# DriverOK-DemuxOK-VIA71.net
KiCad netlist of a schematic drawn in EAGLE
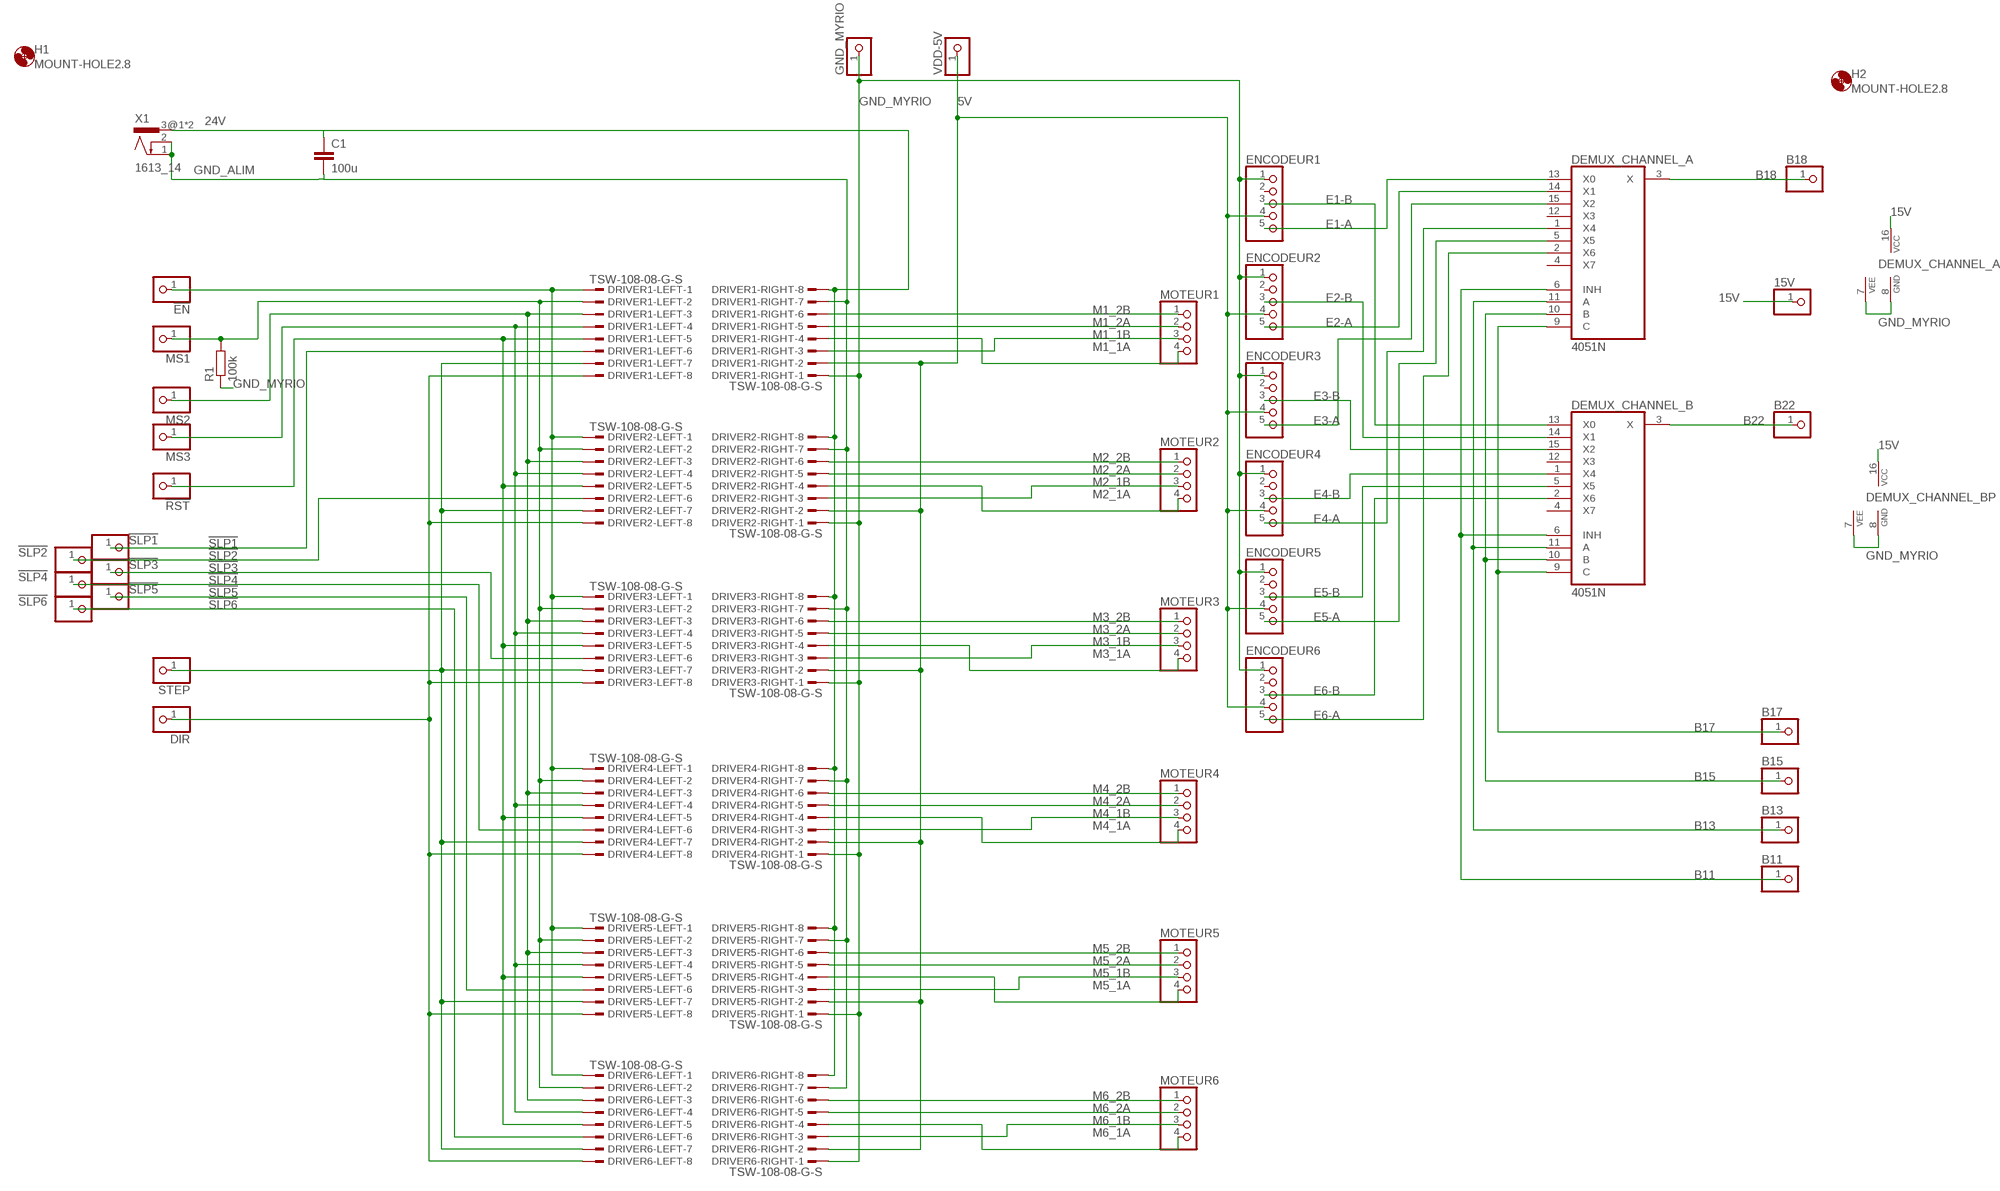
[diagram p0: schematic, sheet 1]

(export (version "E")
  (design (tool "Eeschema 10.0.6"))
  (components
    (comp (ref "!EN")
      (value "PINHD-1X1")
      (footprint "eagle-import:1X01")
      (libsource (lib "eagle-import") (part "PINHD-1X1"))
    )
    (comp (ref "!RST")
      (value "PINHD-1X1")
      (footprint "eagle-import:1X01")
      (libsource (lib "eagle-import") (part "PINHD-1X1"))
    )
    (comp (ref "!SLP1")
      (value "PINHD-1X1")
      (footprint "eagle-import:1X01")
      (libsource (lib "eagle-import") (part "PINHD-1X1"))
    )
    (comp (ref "!SLP2")
      (value "PINHD-1X1")
      (footprint "eagle-import:1X01")
      (libsource (lib "eagle-import") (part "PINHD-1X1"))
    )
    (comp (ref "!SLP3")
      (value "PINHD-1X1")
      (footprint "eagle-import:1X01")
      (libsource (lib "eagle-import") (part "PINHD-1X1"))
    )
    (comp (ref "!SLP4")
      (value "PINHD-1X1")
      (footprint "eagle-import:1X01")
      (libsource (lib "eagle-import") (part "PINHD-1X1"))
    )
    (comp (ref "!SLP5")
      (value "PINHD-1X1")
      (footprint "eagle-import:1X01")
      (libsource (lib "eagle-import") (part "PINHD-1X1"))
    )
    (comp (ref "!SLP6")
      (value "PINHD-1X1")
      (footprint "eagle-import:1X01")
      (libsource (lib "eagle-import") (part "PINHD-1X1"))
    )
    (comp (ref "15V")
      (value "PINHD-1X1")
      (footprint "eagle-import:1X01")
      (libsource (lib "eagle-import") (part "PINHD-1X1"))
    )
    (comp (ref "B11")
      (value "PINHD-1X1")
      (footprint "eagle-import:1X01")
      (libsource (lib "eagle-import") (part "PINHD-1X1"))
    )
    (comp (ref "B13")
      (value "PINHD-1X1")
      (footprint "eagle-import:1X01")
      (libsource (lib "eagle-import") (part "PINHD-1X1"))
    )
    (comp (ref "B15")
      (value "PINHD-1X1")
      (footprint "eagle-import:1X01")
      (libsource (lib "eagle-import") (part "PINHD-1X1"))
    )
    (comp (ref "B17")
      (value "PINHD-1X1")
      (footprint "eagle-import:1X01")
      (libsource (lib "eagle-import") (part "PINHD-1X1"))
    )
    (comp (ref "B18")
      (value "PINHD-1X1")
      (footprint "eagle-import:1X01")
      (libsource (lib "eagle-import") (part "PINHD-1X1"))
    )
    (comp (ref "B22")
      (value "PINHD-1X1")
      (footprint "eagle-import:1X01")
      (libsource (lib "eagle-import") (part "PINHD-1X1"))
    )
    (comp (ref "C1")
      (value "100u")
      (footprint "eagle-import:C025-025X050")
      (libsource (lib "eagle-import") (part "C-EU025-025X050"))
    )
    (comp (ref "DEMUX_CHANNEL_A")
      (value "4051N")
      (footprint "eagle-import:DIL16")
      (libsource (lib "eagle-import") (part "4051N"))
    )
    (comp (ref "DEMUX_CHANNEL_B")
      (value "4051N")
      (footprint "eagle-import:DIL16")
      (libsource (lib "eagle-import") (part "4051N"))
    )
    (comp (ref "DIR")
      (value "PINHD-1X1")
      (footprint "eagle-import:1X01")
      (libsource (lib "eagle-import") (part "PINHD-1X1"))
    )
    (comp (ref "DRIVER1-LEFT")
      (value "TSW-108-08-G-S")
      (footprint "eagle-import:TSW-108-XX-G-S")
      (fields (field (name "MF") "Samtec Inc.") (field (name "MPN") "TSW-108-07-G-S"))
      (libsource (lib "eagle-import") (part "TSW-108--G-S08"))
    )
    (comp (ref "DRIVER1-RIGHT")
      (value "TSW-108-08-G-S")
      (footprint "eagle-import:TSW-108-XX-G-S")
      (fields (field (name "MF") "Samtec Inc.") (field (name "MPN") "TSW-108-07-G-S"))
      (libsource (lib "eagle-import") (part "TSW-108--G-S08"))
    )
    (comp (ref "DRIVER2-LEFT")
      (value "TSW-108-08-G-S")
      (footprint "eagle-import:TSW-108-XX-G-S")
      (fields (field (name "MF") "Samtec Inc.") (field (name "MPN") "TSW-108-07-G-S"))
      (libsource (lib "eagle-import") (part "TSW-108--G-S08"))
    )
    (comp (ref "DRIVER2-RIGHT")
      (value "TSW-108-08-G-S")
      (footprint "eagle-import:TSW-108-XX-G-S")
      (fields (field (name "MF") "Samtec Inc.") (field (name "MPN") "TSW-108-07-G-S"))
      (libsource (lib "eagle-import") (part "TSW-108--G-S08"))
    )
    (comp (ref "DRIVER3-LEFT")
      (value "TSW-108-08-G-S")
      (footprint "eagle-import:TSW-108-XX-G-S")
      (fields (field (name "MF") "Samtec Inc.") (field (name "MPN") "TSW-108-07-G-S"))
      (libsource (lib "eagle-import") (part "TSW-108--G-S08"))
    )
    (comp (ref "DRIVER3-RIGHT")
      (value "TSW-108-08-G-S")
      (footprint "eagle-import:TSW-108-XX-G-S")
      (fields (field (name "MF") "Samtec Inc.") (field (name "MPN") "TSW-108-07-G-S"))
      (libsource (lib "eagle-import") (part "TSW-108--G-S08"))
    )
    (comp (ref "DRIVER4-LEFT")
      (value "TSW-108-08-G-S")
      (footprint "eagle-import:TSW-108-XX-G-S")
      (fields (field (name "MF") "Samtec Inc.") (field (name "MPN") "TSW-108-07-G-S"))
      (libsource (lib "eagle-import") (part "TSW-108--G-S08"))
    )
    (comp (ref "DRIVER4-RIGHT")
      (value "TSW-108-08-G-S")
      (footprint "eagle-import:TSW-108-XX-G-S")
      (fields (field (name "MF") "Samtec Inc.") (field (name "MPN") "TSW-108-07-G-S"))
      (libsource (lib "eagle-import") (part "TSW-108--G-S08"))
    )
    (comp (ref "DRIVER5-LEFT")
      (value "TSW-108-08-G-S")
      (footprint "eagle-import:TSW-108-XX-G-S")
      (fields (field (name "MF") "Samtec Inc.") (field (name "MPN") "TSW-108-07-G-S"))
      (libsource (lib "eagle-import") (part "TSW-108--G-S08"))
    )
    (comp (ref "DRIVER5-RIGHT")
      (value "TSW-108-08-G-S")
      (footprint "eagle-import:TSW-108-XX-G-S")
      (fields (field (name "MF") "Samtec Inc.") (field (name "MPN") "TSW-108-07-G-S"))
      (libsource (lib "eagle-import") (part "TSW-108--G-S08"))
    )
    (comp (ref "DRIVER6-LEFT")
      (value "TSW-108-08-G-S")
      (footprint "eagle-import:TSW-108-XX-G-S")
      (fields (field (name "MF") "Samtec Inc.") (field (name "MPN") "TSW-108-07-G-S"))
      (libsource (lib "eagle-import") (part "TSW-108--G-S08"))
    )
    (comp (ref "DRIVER6-RIGHT")
      (value "TSW-108-08-G-S")
      (footprint "eagle-import:TSW-108-XX-G-S")
      (fields (field (name "MF") "Samtec Inc.") (field (name "MPN") "TSW-108-07-G-S"))
      (libsource (lib "eagle-import") (part "TSW-108--G-S08"))
    )
    (comp (ref "ENCODEUR1")
      (value "PINHD-1X5")
      (footprint "eagle-import:1X05")
      (libsource (lib "eagle-import") (part "PINHD-1X5"))
    )
    (comp (ref "ENCODEUR2")
      (value "PINHD-1X5")
      (footprint "eagle-import:1X05")
      (libsource (lib "eagle-import") (part "PINHD-1X5"))
    )
    (comp (ref "ENCODEUR3")
      (value "PINHD-1X5")
      (footprint "eagle-import:1X05")
      (libsource (lib "eagle-import") (part "PINHD-1X5"))
    )
    (comp (ref "ENCODEUR4")
      (value "PINHD-1X5")
      (footprint "eagle-import:1X05")
      (libsource (lib "eagle-import") (part "PINHD-1X5"))
    )
    (comp (ref "ENCODEUR5")
      (value "PINHD-1X5")
      (footprint "eagle-import:1X05")
      (libsource (lib "eagle-import") (part "PINHD-1X5"))
    )
    (comp (ref "ENCODEUR6")
      (value "PINHD-1X5")
      (footprint "eagle-import:1X05")
      (libsource (lib "eagle-import") (part "PINHD-1X5"))
    )
    (comp (ref "GND_MYRIO")
      (value "PINHD-1X1")
      (footprint "eagle-import:1X01")
      (libsource (lib "eagle-import") (part "PINHD-1X1"))
    )
    (comp (ref "H1")
      (value "MOUNT-HOLE2.8")
      (footprint "eagle-import:2,8")
      (libsource (lib "eagle-import") (part "MOUNT-HOLE2.8"))
    )
    (comp (ref "H2")
      (value "MOUNT-HOLE2.8")
      (footprint "eagle-import:2,8")
      (libsource (lib "eagle-import") (part "MOUNT-HOLE2.8"))
    )
    (comp (ref "MOTEUR1")
      (value "PINHD-1X4")
      (footprint "eagle-import:1X04")
      (libsource (lib "eagle-import") (part "PINHD-1X4"))
    )
    (comp (ref "MOTEUR2")
      (value "PINHD-1X4")
      (footprint "eagle-import:1X04")
      (libsource (lib "eagle-import") (part "PINHD-1X4"))
    )
    (comp (ref "MOTEUR3")
      (value "PINHD-1X4")
      (footprint "eagle-import:1X04")
      (libsource (lib "eagle-import") (part "PINHD-1X4"))
    )
    (comp (ref "MOTEUR4")
      (value "PINHD-1X4")
      (footprint "eagle-import:1X04")
      (libsource (lib "eagle-import") (part "PINHD-1X4"))
    )
    (comp (ref "MOTEUR5")
      (value "PINHD-1X4")
      (footprint "eagle-import:1X04")
      (libsource (lib "eagle-import") (part "PINHD-1X4"))
    )
    (comp (ref "MOTEUR6")
      (value "PINHD-1X4")
      (footprint "eagle-import:1X04")
      (libsource (lib "eagle-import") (part "PINHD-1X4"))
    )
    (comp (ref "MS1")
      (value "PINHD-1X1")
      (footprint "eagle-import:1X01")
      (libsource (lib "eagle-import") (part "PINHD-1X1"))
    )
    (comp (ref "MS2")
      (value "PINHD-1X1")
      (footprint "eagle-import:1X01")
      (libsource (lib "eagle-import") (part "PINHD-1X1"))
    )
    (comp (ref "MS3")
      (value "PINHD-1X1")
      (footprint "eagle-import:1X01")
      (libsource (lib "eagle-import") (part "PINHD-1X1"))
    )
    (comp (ref "R1")
      (value "100k")
      (footprint "eagle-import:0207_10")
      (libsource (lib "eagle-import") (part "R-EU_0207/10"))
    )
    (comp (ref "STEP")
      (value "PINHD-1X1")
      (footprint "eagle-import:1X01")
      (libsource (lib "eagle-import") (part "PINHD-1X1"))
    )
    (comp (ref "VDD-5V")
      (value "PINHD-1X1")
      (footprint "eagle-import:1X01")
      (libsource (lib "eagle-import") (part "PINHD-1X1"))
    )
    (comp (ref "X1")
      (value "1613_14")
      (footprint "eagle-import:1613_14")
      (fields (field (name "MF") "LUMBERG") (field (name "MPN") "1613 14"))
      (libsource (lib "eagle-import") (part "1613_14"))
    )
  )
  (nets
    (net (code "1") (name "/5V") (class "Default")
      (node (ref "DRIVER1-RIGHT") (pin "2") (pinfunction "1_2") (pintype "passive"))
      (node (ref "DRIVER2-RIGHT") (pin "2") (pinfunction "1_2") (pintype "passive"))
      (node (ref "DRIVER3-RIGHT") (pin "2") (pinfunction "1_2") (pintype "passive"))
      (node (ref "DRIVER4-RIGHT") (pin "2") (pinfunction "1_2") (pintype "passive"))
      (node (ref "DRIVER5-RIGHT") (pin "2") (pinfunction "1_2") (pintype "passive"))
      (node (ref "DRIVER6-RIGHT") (pin "2") (pinfunction "1_2") (pintype "passive"))
      (node (ref "ENCODEUR1") (pin "4") (pinfunction "4_4") (pintype "passive"))
      (node (ref "ENCODEUR2") (pin "4") (pinfunction "4_4") (pintype "passive"))
      (node (ref "ENCODEUR3") (pin "4") (pinfunction "4_4") (pintype "passive"))
      (node (ref "ENCODEUR4") (pin "4") (pinfunction "4_4") (pintype "passive"))
      (node (ref "ENCODEUR5") (pin "4") (pinfunction "4_4") (pintype "passive"))
      (node (ref "ENCODEUR6") (pin "4") (pinfunction "4_4") (pintype "passive"))
      (node (ref "VDD-5V") (pin "1") (pinfunction "1_1") (pintype "passive"))
    )
    (net (code "2") (name "/15V") (class "Default")
      (node (ref "15V") (pin "1") (pinfunction "1_1") (pintype "passive"))
      (node (ref "DEMUX_CHANNEL_A") (pin "16") (pinfunction "VCC_16") (pintype "power_in"))
      (node (ref "DEMUX_CHANNEL_B") (pin "16") (pinfunction "VCC_16") (pintype "power_in"))
    )
    (net (code "3") (name "/24V") (class "Default")
      (node (ref "C1") (pin "1") (pinfunction "1_1") (pintype "passive"))
      (node (ref "DRIVER1-RIGHT") (pin "8") (pinfunction "1_8") (pintype "passive"))
      (node (ref "DRIVER2-RIGHT") (pin "8") (pinfunction "1_8") (pintype "passive"))
      (node (ref "DRIVER3-RIGHT") (pin "8") (pinfunction "1_8") (pintype "passive"))
      (node (ref "DRIVER4-RIGHT") (pin "8") (pinfunction "1_8") (pintype "passive"))
      (node (ref "DRIVER5-RIGHT") (pin "8") (pinfunction "1_8") (pintype "passive"))
      (node (ref "DRIVER6-RIGHT") (pin "8") (pinfunction "1_8") (pintype "passive"))
      (node (ref "X1") (pin "3@1") (pinfunction "3_3@1") (pintype "passive"))
      (node (ref "X1") (pin "3@2") (pinfunction "3_3@2") (pintype "passive"))
    )
    (net (code "4") (name "/B11") (class "Default")
      (node (ref "B11") (pin "1") (pinfunction "1_1") (pintype "passive"))
      (node (ref "DEMUX_CHANNEL_A") (pin "6") (pinfunction "INH_6") (pintype "input"))
      (node (ref "DEMUX_CHANNEL_B") (pin "6") (pinfunction "INH_6") (pintype "input"))
    )
    (net (code "5") (name "/B13") (class "Default")
      (node (ref "B13") (pin "1") (pinfunction "1_1") (pintype "passive"))
      (node (ref "DEMUX_CHANNEL_A") (pin "11") (pinfunction "A_11") (pintype "input"))
      (node (ref "DEMUX_CHANNEL_B") (pin "11") (pinfunction "A_11") (pintype "input"))
    )
    (net (code "6") (name "/B15") (class "Default")
      (node (ref "B15") (pin "1") (pinfunction "1_1") (pintype "passive"))
      (node (ref "DEMUX_CHANNEL_A") (pin "10") (pinfunction "B_10") (pintype "input"))
      (node (ref "DEMUX_CHANNEL_B") (pin "10") (pinfunction "B_10") (pintype "input"))
    )
    (net (code "7") (name "/B17") (class "Default")
      (node (ref "B17") (pin "1") (pinfunction "1_1") (pintype "passive"))
      (node (ref "DEMUX_CHANNEL_A") (pin "9") (pinfunction "C_9") (pintype "input"))
      (node (ref "DEMUX_CHANNEL_B") (pin "9") (pinfunction "C_9") (pintype "input"))
    )
    (net (code "8") (name "/B18") (class "Default")
      (node (ref "B18") (pin "1") (pinfunction "1_1") (pintype "passive"))
      (node (ref "DEMUX_CHANNEL_A") (pin "3") (pinfunction "X_3") (pintype "bidirectional"))
    )
    (net (code "9") (name "/B22") (class "Default")
      (node (ref "B22") (pin "1") (pinfunction "1_1") (pintype "passive"))
      (node (ref "DEMUX_CHANNEL_B") (pin "3") (pinfunction "X_3") (pintype "bidirectional"))
    )
    (net (code "10") (name "/E1-A") (class "Default")
      (node (ref "DEMUX_CHANNEL_A") (pin "13") (pinfunction "X0_13") (pintype "bidirectional"))
      (node (ref "ENCODEUR1") (pin "5") (pinfunction "5_5") (pintype "passive"))
    )
    (net (code "11") (name "/E1-B") (class "Default")
      (node (ref "DEMUX_CHANNEL_B") (pin "13") (pinfunction "X0_13") (pintype "bidirectional"))
      (node (ref "ENCODEUR1") (pin "3") (pinfunction "3_3") (pintype "passive"))
    )
    (net (code "12") (name "/E2-A") (class "Default")
      (node (ref "DEMUX_CHANNEL_A") (pin "14") (pinfunction "X1_14") (pintype "bidirectional"))
      (node (ref "ENCODEUR2") (pin "5") (pinfunction "5_5") (pintype "passive"))
    )
    (net (code "13") (name "/E2-B") (class "Default")
      (node (ref "DEMUX_CHANNEL_B") (pin "14") (pinfunction "X1_14") (pintype "bidirectional"))
      (node (ref "ENCODEUR2") (pin "3") (pinfunction "3_3") (pintype "passive"))
    )
    (net (code "14") (name "/E3-A") (class "Default")
      (node (ref "DEMUX_CHANNEL_A") (pin "15") (pinfunction "X2_15") (pintype "bidirectional"))
      (node (ref "ENCODEUR3") (pin "5") (pinfunction "5_5") (pintype "passive"))
    )
    (net (code "15") (name "/E3-B") (class "Default")
      (node (ref "DEMUX_CHANNEL_B") (pin "15") (pinfunction "X2_15") (pintype "bidirectional"))
      (node (ref "ENCODEUR3") (pin "3") (pinfunction "3_3") (pintype "passive"))
    )
    (net (code "16") (name "/E4-A") (class "Default")
      (node (ref "DEMUX_CHANNEL_A") (pin "1") (pinfunction "X4_1") (pintype "bidirectional"))
      (node (ref "ENCODEUR4") (pin "5") (pinfunction "5_5") (pintype "passive"))
    )
    (net (code "17") (name "/E4-B") (class "Default")
      (node (ref "DEMUX_CHANNEL_B") (pin "1") (pinfunction "X4_1") (pintype "bidirectional"))
      (node (ref "ENCODEUR4") (pin "3") (pinfunction "3_3") (pintype "passive"))
    )
    (net (code "18") (name "/E5-A") (class "Default")
      (node (ref "DEMUX_CHANNEL_A") (pin "5") (pinfunction "X5_5") (pintype "bidirectional"))
      (node (ref "ENCODEUR5") (pin "5") (pinfunction "5_5") (pintype "passive"))
    )
    (net (code "19") (name "/E5-B") (class "Default")
      (node (ref "DEMUX_CHANNEL_B") (pin "5") (pinfunction "X5_5") (pintype "bidirectional"))
      (node (ref "ENCODEUR5") (pin "3") (pinfunction "3_3") (pintype "passive"))
    )
    (net (code "20") (name "/E6-A") (class "Default")
      (node (ref "DEMUX_CHANNEL_A") (pin "2") (pinfunction "X6_2") (pintype "bidirectional"))
      (node (ref "ENCODEUR6") (pin "5") (pinfunction "5_5") (pintype "passive"))
    )
    (net (code "21") (name "/E6-B") (class "Default")
      (node (ref "DEMUX_CHANNEL_B") (pin "2") (pinfunction "X6_2") (pintype "bidirectional"))
      (node (ref "ENCODEUR6") (pin "3") (pinfunction "3_3") (pintype "passive"))
    )
    (net (code "22") (name "/GND_ALIM") (class "Default")
      (node (ref "C1") (pin "2") (pinfunction "2_2") (pintype "passive"))
      (node (ref "DRIVER1-RIGHT") (pin "7") (pinfunction "1_7") (pintype "passive"))
      (node (ref "DRIVER2-RIGHT") (pin "7") (pinfunction "1_7") (pintype "passive"))
      (node (ref "DRIVER3-RIGHT") (pin "7") (pinfunction "1_7") (pintype "passive"))
      (node (ref "DRIVER4-RIGHT") (pin "7") (pinfunction "1_7") (pintype "passive"))
      (node (ref "DRIVER5-RIGHT") (pin "7") (pinfunction "1_7") (pintype "passive"))
      (node (ref "DRIVER6-RIGHT") (pin "7") (pinfunction "1_7") (pintype "passive"))
      (node (ref "X1") (pin "1") (pinfunction "1_1") (pintype "passive"))
      (node (ref "X1") (pin "2") (pinfunction "2_2") (pintype "passive"))
    )
    (net (code "23") (name "/GND_MYRIO") (class "Default")
      (node (ref "DEMUX_CHANNEL_A") (pin "7") (pinfunction "VEE_7") (pintype "power_in"))
      (node (ref "DEMUX_CHANNEL_A") (pin "8") (pinfunction "GND_8") (pintype "power_in"))
      (node (ref "DEMUX_CHANNEL_B") (pin "7") (pinfunction "VEE_7") (pintype "power_in"))
      (node (ref "DEMUX_CHANNEL_B") (pin "8") (pinfunction "GND_8") (pintype "power_in"))
      (node (ref "DRIVER1-RIGHT") (pin "1") (pinfunction "1_1") (pintype "passive"))
      (node (ref "DRIVER2-RIGHT") (pin "1") (pinfunction "1_1") (pintype "passive"))
      (node (ref "DRIVER3-RIGHT") (pin "1") (pinfunction "1_1") (pintype "passive"))
      (node (ref "DRIVER4-RIGHT") (pin "1") (pinfunction "1_1") (pintype "passive"))
      (node (ref "DRIVER5-RIGHT") (pin "1") (pinfunction "1_1") (pintype "passive"))
      (node (ref "DRIVER6-RIGHT") (pin "1") (pinfunction "1_1") (pintype "passive"))
      (node (ref "ENCODEUR1") (pin "1") (pinfunction "1_1") (pintype "passive"))
      (node (ref "ENCODEUR2") (pin "1") (pinfunction "1_1") (pintype "passive"))
      (node (ref "ENCODEUR3") (pin "1") (pinfunction "1_1") (pintype "passive"))
      (node (ref "ENCODEUR4") (pin "1") (pinfunction "1_1") (pintype "passive"))
      (node (ref "ENCODEUR5") (pin "1") (pinfunction "1_1") (pintype "passive"))
      (node (ref "ENCODEUR6") (pin "1") (pinfunction "1_1") (pintype "passive"))
      (node (ref "GND_MYRIO") (pin "1") (pinfunction "1_1") (pintype "passive"))
      (node (ref "R1") (pin "1") (pinfunction "1_1") (pintype "passive"))
    )
    (net (code "24") (name "/M1_1A") (class "Default")
      (node (ref "DRIVER1-RIGHT") (pin "4") (pinfunction "1_4") (pintype "passive"))
      (node (ref "MOTEUR1") (pin "4") (pinfunction "4_4") (pintype "passive"))
    )
    (net (code "25") (name "/M1_1B") (class "Default")
      (node (ref "DRIVER1-RIGHT") (pin "3") (pinfunction "1_3") (pintype "passive"))
      (node (ref "MOTEUR1") (pin "3") (pinfunction "3_3") (pintype "passive"))
    )
    (net (code "26") (name "/M1_2A") (class "Default")
      (node (ref "DRIVER1-RIGHT") (pin "5") (pinfunction "1_5") (pintype "passive"))
      (node (ref "MOTEUR1") (pin "2") (pinfunction "2_2") (pintype "passive"))
    )
    (net (code "27") (name "/M1_2B") (class "Default")
      (node (ref "DRIVER1-RIGHT") (pin "6") (pinfunction "1_6") (pintype "passive"))
      (node (ref "MOTEUR1") (pin "1") (pinfunction "1_1") (pintype "passive"))
    )
    (net (code "28") (name "/M2_1A") (class "Default")
      (node (ref "DRIVER2-RIGHT") (pin "4") (pinfunction "1_4") (pintype "passive"))
      (node (ref "MOTEUR2") (pin "4") (pinfunction "4_4") (pintype "passive"))
    )
    (net (code "29") (name "/M2_1B") (class "Default")
      (node (ref "DRIVER2-RIGHT") (pin "3") (pinfunction "1_3") (pintype "passive"))
      (node (ref "MOTEUR2") (pin "3") (pinfunction "3_3") (pintype "passive"))
    )
    (net (code "30") (name "/M2_2A") (class "Default")
      (node (ref "DRIVER2-RIGHT") (pin "5") (pinfunction "1_5") (pintype "passive"))
      (node (ref "MOTEUR2") (pin "2") (pinfunction "2_2") (pintype "passive"))
    )
    (net (code "31") (name "/M2_2B") (class "Default")
      (node (ref "DRIVER2-RIGHT") (pin "6") (pinfunction "1_6") (pintype "passive"))
      (node (ref "MOTEUR2") (pin "1") (pinfunction "1_1") (pintype "passive"))
    )
    (net (code "32") (name "/M3_1A") (class "Default")
      (node (ref "DRIVER3-RIGHT") (pin "4") (pinfunction "1_4") (pintype "passive"))
      (node (ref "MOTEUR3") (pin "4") (pinfunction "4_4") (pintype "passive"))
    )
    (net (code "33") (name "/M3_1B") (class "Default")
      (node (ref "DRIVER3-RIGHT") (pin "3") (pinfunction "1_3") (pintype "passive"))
      (node (ref "MOTEUR3") (pin "3") (pinfunction "3_3") (pintype "passive"))
    )
    (net (code "34") (name "/M3_2A") (class "Default")
      (node (ref "DRIVER3-RIGHT") (pin "5") (pinfunction "1_5") (pintype "passive"))
      (node (ref "MOTEUR3") (pin "2") (pinfunction "2_2") (pintype "passive"))
    )
    (net (code "35") (name "/M3_2B") (class "Default")
      (node (ref "DRIVER3-RIGHT") (pin "6") (pinfunction "1_6") (pintype "passive"))
      (node (ref "MOTEUR3") (pin "1") (pinfunction "1_1") (pintype "passive"))
    )
    (net (code "36") (name "/M4_1A") (class "Default")
      (node (ref "DRIVER4-RIGHT") (pin "4") (pinfunction "1_4") (pintype "passive"))
      (node (ref "MOTEUR4") (pin "4") (pinfunction "4_4") (pintype "passive"))
    )
    (net (code "37") (name "/M4_1B") (class "Default")
      (node (ref "DRIVER4-RIGHT") (pin "3") (pinfunction "1_3") (pintype "passive"))
      (node (ref "MOTEUR4") (pin "3") (pinfunction "3_3") (pintype "passive"))
    )
    (net (code "38") (name "/M4_2A") (class "Default")
      (node (ref "DRIVER4-RIGHT") (pin "5") (pinfunction "1_5") (pintype "passive"))
      (node (ref "MOTEUR4") (pin "2") (pinfunction "2_2") (pintype "passive"))
    )
    (net (code "39") (name "/M4_2B") (class "Default")
      (node (ref "DRIVER4-RIGHT") (pin "6") (pinfunction "1_6") (pintype "passive"))
      (node (ref "MOTEUR4") (pin "1") (pinfunction "1_1") (pintype "passive"))
    )
    (net (code "40") (name "/M5_1A") (class "Default")
      (node (ref "DRIVER5-RIGHT") (pin "4") (pinfunction "1_4") (pintype "passive"))
      (node (ref "MOTEUR5") (pin "4") (pinfunction "4_4") (pintype "passive"))
    )
    (net (code "41") (name "/M5_1B") (class "Default")
      (node (ref "DRIVER5-RIGHT") (pin "3") (pinfunction "1_3") (pintype "passive"))
      (node (ref "MOTEUR5") (pin "3") (pinfunction "3_3") (pintype "passive"))
    )
    (net (code "42") (name "/M5_2A") (class "Default")
      (node (ref "DRIVER5-RIGHT") (pin "5") (pinfunction "1_5") (pintype "passive"))
      (node (ref "MOTEUR5") (pin "2") (pinfunction "2_2") (pintype "passive"))
    )
    (net (code "43") (name "/M5_2B") (class "Default")
      (node (ref "DRIVER5-RIGHT") (pin "6") (pinfunction "1_6") (pintype "passive"))
      (node (ref "MOTEUR5") (pin "1") (pinfunction "1_1") (pintype "passive"))
    )
    (net (code "44") (name "/M6_1A") (class "Default")
      (node (ref "DRIVER6-RIGHT") (pin "4") (pinfunction "1_4") (pintype "passive"))
      (node (ref "MOTEUR6") (pin "4") (pinfunction "4_4") (pintype "passive"))
    )
    (net (code "45") (name "/M6_1B") (class "Default")
      (node (ref "DRIVER6-RIGHT") (pin "3") (pinfunction "1_3") (pintype "passive"))
      (node (ref "MOTEUR6") (pin "3") (pinfunction "3_3") (pintype "passive"))
    )
    (net (code "46") (name "/M6_2A") (class "Default")
      (node (ref "DRIVER6-RIGHT") (pin "5") (pinfunction "1_5") (pintype "passive"))
      (node (ref "MOTEUR6") (pin "2") (pinfunction "2_2") (pintype "passive"))
    )
    (net (code "47") (name "/M6_2B") (class "Default")
      (node (ref "DRIVER6-RIGHT") (pin "6") (pinfunction "1_6") (pintype "passive"))
      (node (ref "MOTEUR6") (pin "1") (pinfunction "1_1") (pintype "passive"))
    )
    (net (code "48") (name "/~{SLP1}") (class "Default")
      (node (ref "!SLP1") (pin "1") (pinfunction "1_1") (pintype "passive"))
      (node (ref "DRIVER1-LEFT") (pin "6") (pinfunction "1_6") (pintype "passive"))
    )
    (net (code "49") (name "/~{SLP2}") (class "Default")
      (node (ref "!SLP2") (pin "1") (pinfunction "1_1") (pintype "passive"))
      (node (ref "DRIVER2-LEFT") (pin "6") (pinfunction "1_6") (pintype "passive"))
    )
    (net (code "50") (name "/~{SLP3}") (class "Default")
      (node (ref "!SLP3") (pin "1") (pinfunction "1_1") (pintype "passive"))
      (node (ref "DRIVER3-LEFT") (pin "6") (pinfunction "1_6") (pintype "passive"))
    )
    (net (code "51") (name "/~{SLP4}") (class "Default")
      (node (ref "!SLP4") (pin "1") (pinfunction "1_1") (pintype "passive"))
      (node (ref "DRIVER4-LEFT") (pin "6") (pinfunction "1_6") (pintype "passive"))
    )
    (net (code "52") (name "/~{SLP5}") (class "Default")
      (node (ref "!SLP5") (pin "1") (pinfunction "1_1") (pintype "passive"))
      (node (ref "DRIVER5-LEFT") (pin "6") (pinfunction "1_6") (pintype "passive"))
    )
    (net (code "53") (name "/~{SLP6}") (class "Default")
      (node (ref "!SLP6") (pin "1") (pinfunction "1_1") (pintype "passive"))
      (node (ref "DRIVER6-LEFT") (pin "6") (pinfunction "1_6") (pintype "passive"))
    )
    (net (code "54") (name "Net-(!EN-Pad1)") (class "Default")
      (node (ref "!EN") (pin "1") (pinfunction "1_1") (pintype "passive"))
      (node (ref "DRIVER1-LEFT") (pin "1") (pinfunction "1_1") (pintype "passive"))
      (node (ref "DRIVER2-LEFT") (pin "1") (pinfunction "1_1") (pintype "passive"))
      (node (ref "DRIVER3-LEFT") (pin "1") (pinfunction "1_1") (pintype "passive"))
      (node (ref "DRIVER4-LEFT") (pin "1") (pinfunction "1_1") (pintype "passive"))
      (node (ref "DRIVER5-LEFT") (pin "1") (pinfunction "1_1") (pintype "passive"))
      (node (ref "DRIVER6-LEFT") (pin "1") (pinfunction "1_1") (pintype "passive"))
    )
    (net (code "55") (name "Net-(DRIVER1-LEFTB-1)") (class "Default")
      (node (ref "DRIVER1-LEFT") (pin "2") (pinfunction "1_2") (pintype "passive"))
      (node (ref "DRIVER2-LEFT") (pin "2") (pinfunction "1_2") (pintype "passive"))
      (node (ref "DRIVER3-LEFT") (pin "2") (pinfunction "1_2") (pintype "passive"))
      (node (ref "DRIVER4-LEFT") (pin "2") (pinfunction "1_2") (pintype "passive"))
      (node (ref "DRIVER5-LEFT") (pin "2") (pinfunction "1_2") (pintype "passive"))
      (node (ref "DRIVER6-LEFT") (pin "2") (pinfunction "1_2") (pintype "passive"))
      (node (ref "MS1") (pin "1") (pinfunction "1_1") (pintype "passive"))
      (node (ref "R1") (pin "2") (pinfunction "2_2") (pintype "passive"))
    )
    (net (code "56") (name "Net-(DRIVER1-LEFTC-1)") (class "Default")
      (node (ref "DRIVER1-LEFT") (pin "3") (pinfunction "1_3") (pintype "passive"))
      (node (ref "DRIVER2-LEFT") (pin "3") (pinfunction "1_3") (pintype "passive"))
      (node (ref "DRIVER3-LEFT") (pin "3") (pinfunction "1_3") (pintype "passive"))
      (node (ref "DRIVER4-LEFT") (pin "3") (pinfunction "1_3") (pintype "passive"))
      (node (ref "DRIVER5-LEFT") (pin "3") (pinfunction "1_3") (pintype "passive"))
      (node (ref "DRIVER6-LEFT") (pin "3") (pinfunction "1_3") (pintype "passive"))
      (node (ref "MS2") (pin "1") (pinfunction "1_1") (pintype "passive"))
    )
    (net (code "57") (name "Net-(DRIVER1-LEFTD-1)") (class "Default")
      (node (ref "DRIVER1-LEFT") (pin "4") (pinfunction "1_4") (pintype "passive"))
      (node (ref "DRIVER2-LEFT") (pin "4") (pinfunction "1_4") (pintype "passive"))
      (node (ref "DRIVER3-LEFT") (pin "4") (pinfunction "1_4") (pintype "passive"))
      (node (ref "DRIVER4-LEFT") (pin "4") (pinfunction "1_4") (pintype "passive"))
      (node (ref "DRIVER5-LEFT") (pin "4") (pinfunction "1_4") (pintype "passive"))
      (node (ref "DRIVER6-LEFT") (pin "4") (pinfunction "1_4") (pintype "passive"))
      (node (ref "MS3") (pin "1") (pinfunction "1_1") (pintype "passive"))
    )
    (net (code "58") (name "Net-(DRIVER1-LEFTE-1)") (class "Default")
      (node (ref "!RST") (pin "1") (pinfunction "1_1") (pintype "passive"))
      (node (ref "DRIVER1-LEFT") (pin "5") (pinfunction "1_5") (pintype "passive"))
      (node (ref "DRIVER2-LEFT") (pin "5") (pinfunction "1_5") (pintype "passive"))
      (node (ref "DRIVER3-LEFT") (pin "5") (pinfunction "1_5") (pintype "passive"))
      (node (ref "DRIVER4-LEFT") (pin "5") (pinfunction "1_5") (pintype "passive"))
      (node (ref "DRIVER5-LEFT") (pin "5") (pinfunction "1_5") (pintype "passive"))
      (node (ref "DRIVER6-LEFT") (pin "5") (pinfunction "1_5") (pintype "passive"))
    )
    (net (code "59") (name "Net-(DRIVER1-LEFTG-1)") (class "Default")
      (node (ref "DRIVER1-LEFT") (pin "7") (pinfunction "1_7") (pintype "passive"))
      (node (ref "DRIVER2-LEFT") (pin "7") (pinfunction "1_7") (pintype "passive"))
      (node (ref "DRIVER3-LEFT") (pin "7") (pinfunction "1_7") (pintype "passive"))
      (node (ref "DRIVER4-LEFT") (pin "7") (pinfunction "1_7") (pintype "passive"))
      (node (ref "DRIVER5-LEFT") (pin "7") (pinfunction "1_7") (pintype "passive"))
      (node (ref "DRIVER6-LEFT") (pin "7") (pinfunction "1_7") (pintype "passive"))
      (node (ref "STEP") (pin "1") (pinfunction "1_1") (pintype "passive"))
    )
    (net (code "60") (name "Net-(DRIVER1-LEFTH-1)") (class "Default")
      (node (ref "DIR") (pin "1") (pinfunction "1_1") (pintype "passive"))
      (node (ref "DRIVER1-LEFT") (pin "8") (pinfunction "1_8") (pintype "passive"))
      (node (ref "DRIVER2-LEFT") (pin "8") (pinfunction "1_8") (pintype "passive"))
      (node (ref "DRIVER3-LEFT") (pin "8") (pinfunction "1_8") (pintype "passive"))
      (node (ref "DRIVER4-LEFT") (pin "8") (pinfunction "1_8") (pintype "passive"))
      (node (ref "DRIVER5-LEFT") (pin "8") (pinfunction "1_8") (pintype "passive"))
      (node (ref "DRIVER6-LEFT") (pin "8") (pinfunction "1_8") (pintype "passive"))
    )
    (net (code "61") (name "unconnected-(DEMUX_CHANNEL_AA-X3-Pad12)") (class "Default")
      (node (ref "DEMUX_CHANNEL_A") (pin "12") (pinfunction "X3_12") (pintype "bidirectional"))
    )
    (net (code "62") (name "unconnected-(DEMUX_CHANNEL_AA-X7-Pad4)") (class "Default")
      (node (ref "DEMUX_CHANNEL_A") (pin "4") (pinfunction "X7_4") (pintype "bidirectional"))
    )
    (net (code "63") (name "unconnected-(DEMUX_CHANNEL_BA-X3-Pad12)") (class "Default")
      (node (ref "DEMUX_CHANNEL_B") (pin "12") (pinfunction "X3_12") (pintype "bidirectional"))
    )
    (net (code "64") (name "unconnected-(DEMUX_CHANNEL_BA-X7-Pad4)") (class "Default")
      (node (ref "DEMUX_CHANNEL_B") (pin "4") (pinfunction "X7_4") (pintype "bidirectional"))
    )
    (net (code "65") (name "unconnected-(ENCODEUR1-Pad2)") (class "Default")
      (node (ref "ENCODEUR1") (pin "2") (pinfunction "2_2") (pintype "passive"))
    )
    (net (code "66") (name "unconnected-(ENCODEUR2-Pad2)") (class "Default")
      (node (ref "ENCODEUR2") (pin "2") (pinfunction "2_2") (pintype "passive"))
    )
    (net (code "67") (name "unconnected-(ENCODEUR3-Pad2)") (class "Default")
      (node (ref "ENCODEUR3") (pin "2") (pinfunction "2_2") (pintype "passive"))
    )
    (net (code "68") (name "unconnected-(ENCODEUR4-Pad2)") (class "Default")
      (node (ref "ENCODEUR4") (pin "2") (pinfunction "2_2") (pintype "passive"))
    )
    (net (code "69") (name "unconnected-(ENCODEUR5-Pad2)") (class "Default")
      (node (ref "ENCODEUR5") (pin "2") (pinfunction "2_2") (pintype "passive"))
    )
    (net (code "70") (name "unconnected-(ENCODEUR6-Pad2)") (class "Default")
      (node (ref "ENCODEUR6") (pin "2") (pinfunction "2_2") (pintype "passive"))
    )
  )
)
